# 2_Part_Conveter.net
KiCad netlist of a schematic drawn in Altium Designer
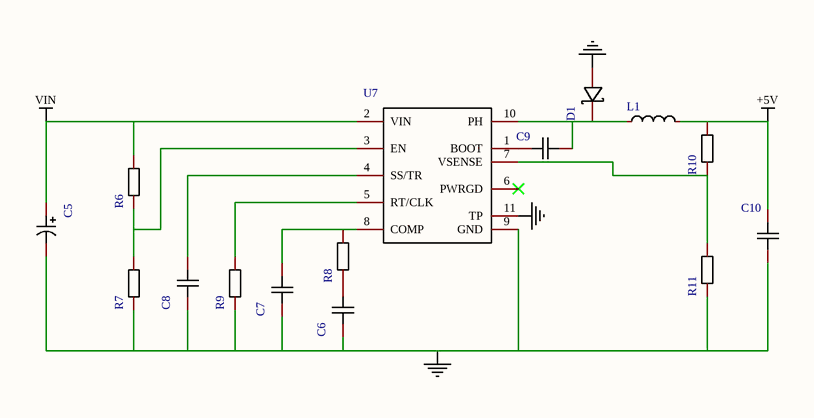
[diagram p0: 2_Part_Conveter.schdoc]

(export (version "E")
  (design (tool "Eeschema 10.0.6"))
  (components
    (comp (ref "C5")
      (value "RVT10UF100V67RV0110_1")
      (description "工作寿命:2000hrs@105℃;")
      (fields
        (field (name "MANUFACTURER") "KNSCHA(科尼盛)")
        (field (name "MANUFACTURER PART") "RVT10UF100V67RV0110")
      )
      (libsource (lib "altium-import") (part "root_3_RVT10UF100V67RV0110_1_"))
    )
    (comp (ref "C6")
      (value "C0603C102K1RAC3083")
      (description "容值:1nF;精度:±10%;额定电压:100V;温度系数:X7R;")
      (fields (field (name "MANUFACTURER") "KEMET(基美)") (field (name "TOLERANCE") "±10%"))
      (libsource (lib "altium-import") (part "root_1_C0603C102K1RAC3083_"))
    )
    (comp (ref "C7")
      (value "C0603C102K1RAC3083")
      (description "容值:1nF;精度:±10%;额定电压:100V;温度系数:X7R;")
      (fields (field (name "MANUFACTURER") "KEMET(基美)") (field (name "TOLERANCE") "±10%"))
      (libsource (lib "altium-import") (part "root_1_C0603C102K1RAC3083_"))
    )
    (comp (ref "C8")
      (value "C0603C102K1RAC3083")
      (description "容值:1nF;精度:±10%;额定电压:100V;温度系数:X7R;")
      (fields (field (name "MANUFACTURER") "KEMET(基美)") (field (name "TOLERANCE") "±10%"))
      (libsource (lib "altium-import") (part "root_1_C0603C102K1RAC3083_"))
    )
    (comp (ref "C9")
      (value "C0603C102K1RAC3083")
      (description "容值:1nF;精度:±10%;额定电压:100V;温度系数:X7R;")
      (fields (field (name "MANUFACTURER") "KEMET(基美)") (field (name "TOLERANCE") "±10%"))
      (libsource (lib "altium-import") (part "root_2_C0603C102K1RAC3083_"))
    )
    (comp (ref "C10")
      (value "GRM32ER60J476ME20L_1")
      (description "容值:47uF;精度:±20%;额定电压:6.3V;温度系数:X5R;")
      (fields
        (field (name "MANUFACTURER") "muRata(村田)")
        (field (name "MANUFACTURER PART") "GRM32ER60J476ME20L")
      )
      (libsource (lib "altium-import") (part "root_0_GRM32ER60J476ME20L_1_"))
    )
    (comp (ref "D1")
      (value "SS24_1")
      (description "直流反向耐压(Vr):40V;平均整流电流(Io):2A;正向压降(Vf):550mV@1A;")
      (fields (field (name "MANUFACTURER") "SINO-IC(光宇睿芯)") (field (name "MANUFACTURER PART") "SS24"))
      (libsource (lib "altium-import") (part "root_1_SS24_1_"))
    )
    (comp (ref "L1")
      (value "CYH74-33UH_1")
      (fields (field (name "MANUFACTURER") "SHOU HAN(首韩)") (field (name "MANUFACTURER PART") "CYH74-33UH"))
      (libsource (lib "altium-import") (part "root_0_CYH74-33UH_1_"))
    )
    (comp (ref "R6")
      (value "CR0603FA5603G_1")
      (description "电阻类型:厚膜电阻;阻值:560kΩ;精度:±1%;功率:1/10W;温度系数:±100ppm/℃;最大工作电压:50V;工作温度范围:-55℃~+125℃;")
      (fields (field (name "MANUFACTURER") "LIZ(丽智电子)") (field (name "MANUFACTURER PART") "CR0603FA5603G"))
      (libsource (lib "altium-import") (part "root_1_CR0603FA5603G_1_"))
    )
    (comp (ref "R7")
      (value "CR0603FA5603G_1")
      (description "电阻类型:厚膜电阻;阻值:560kΩ;精度:±1%;功率:1/10W;温度系数:±100ppm/℃;最大工作电压:50V;工作温度范围:-55℃~+125℃;")
      (fields (field (name "MANUFACTURER") "LIZ(丽智电子)") (field (name "MANUFACTURER PART") "CR0603FA5603G"))
      (libsource (lib "altium-import") (part "root_1_CR0603FA5603G_1_"))
    )
    (comp (ref "R8")
      (value "CR0603FA5603G_1")
      (description "电阻类型:厚膜电阻;阻值:560kΩ;精度:±1%;功率:1/10W;温度系数:±100ppm/℃;最大工作电压:50V;工作温度范围:-55℃~+125℃;")
      (fields (field (name "MANUFACTURER") "LIZ(丽智电子)") (field (name "MANUFACTURER PART") "CR0603FA5603G"))
      (libsource (lib "altium-import") (part "root_1_CR0603FA5603G_1_"))
    )
    (comp (ref "R9")
      (value "CR0603FA5603G_1")
      (description "电阻类型:厚膜电阻;阻值:560kΩ;精度:±1%;功率:1/10W;温度系数:±100ppm/℃;最大工作电压:50V;工作温度范围:-55℃~+125℃;")
      (fields (field (name "MANUFACTURER") "LIZ(丽智电子)") (field (name "MANUFACTURER PART") "CR0603FA5603G"))
      (libsource (lib "altium-import") (part "root_1_CR0603FA5603G_1_"))
    )
    (comp (ref "R10")
      (value "CR0603FA5603G_1")
      (description "电阻类型:厚膜电阻;阻值:560kΩ;精度:±1%;功率:1/10W;温度系数:±100ppm/℃;最大工作电压:50V;工作温度范围:-55℃~+125℃;")
      (fields (field (name "MANUFACTURER") "LIZ(丽智电子)") (field (name "MANUFACTURER PART") "CR0603FA5603G"))
      (libsource (lib "altium-import") (part "root_1_CR0603FA5603G_1_"))
    )
    (comp (ref "R11")
      (value "CR0603FA5603G_1")
      (description "电阻类型:厚膜电阻;阻值:560kΩ;精度:±1%;功率:1/10W;温度系数:±100ppm/℃;最大工作电压:50V;工作温度范围:-55℃~+125℃;")
      (fields (field (name "MANUFACTURER") "LIZ(丽智电子)") (field (name "MANUFACTURER PART") "CR0603FA5603G"))
      (libsource (lib "altium-import") (part "root_1_CR0603FA5603G_1_"))
    )
    (comp (ref "U7")
      (value "TPS54160DGQR_1")
      (description "功能类型:降压型;同步整流:-;输出通道数:-;拓扑结构:-;输入电压:-;输出电流(最大值):-;开关频率:-;")
      (fields (field (name "MANUFACTURER") "TI(德州仪器)") (field (name "MANUFACTURER PART") "TPS54160DGQR"))
      (libsource (lib "altium-import") (part "root_0_TPS54160DGQR_1_"))
    )
  )
  (nets
    (net (code "1") (name "+5V") (class "Default")
      (node (ref "C10") (pin "2") (pinfunction "2_2") (pintype "passive"))
      (node (ref "L1") (pin "2") (pinfunction "2_2") (pintype "passive"))
      (node (ref "R10") (pin "2") (pinfunction "2_2") (pintype "passive"))
    )
    (net (code "2") (name "GND") (class "Default")
      (node (ref "C10") (pin "1") (pinfunction "1_1") (pintype "passive"))
      (node (ref "C5") (pin "2") (pinfunction "2_2") (pintype "passive"))
      (node (ref "C6") (pin "1") (pinfunction "1_1") (pintype "passive"))
      (node (ref "C7") (pin "1") (pinfunction "1_1") (pintype "passive"))
      (node (ref "C8") (pin "1") (pinfunction "1_1") (pintype "passive"))
      (node (ref "D1") (pin "2") (pinfunction "A_2") (pintype "passive"))
      (node (ref "R11") (pin "1") (pinfunction "1_1") (pintype "passive"))
      (node (ref "R7") (pin "1") (pinfunction "1_1") (pintype "passive"))
      (node (ref "R9") (pin "1") (pinfunction "1_1") (pintype "passive"))
      (node (ref "U7") (pin "11") (pinfunction "TP_11") (pintype "passive"))
      (node (ref "U7") (pin "9") (pinfunction "GND_9") (pintype "passive"))
    )
    (net (code "3") (name "Net-(C6-Pad2)") (class "Default")
      (node (ref "C6") (pin "2") (pinfunction "2_2") (pintype "passive"))
      (node (ref "R8") (pin "1") (pinfunction "1_1") (pintype "passive"))
    )
    (net (code "4") (name "Net-(D1-C)") (class "Default")
      (node (ref "C9") (pin "1") (pinfunction "1_1") (pintype "passive"))
      (node (ref "D1") (pin "1") (pinfunction "C_1") (pintype "passive"))
      (node (ref "L1") (pin "1") (pinfunction "1_1") (pintype "passive"))
      (node (ref "U7") (pin "10") (pinfunction "PH_10") (pintype "passive"))
    )
    (net (code "5") (name "Net-(U7-BOOT)") (class "Default")
      (node (ref "C9") (pin "2") (pinfunction "2_2") (pintype "passive"))
      (node (ref "U7") (pin "1") (pinfunction "BOOT_1") (pintype "passive"))
    )
    (net (code "6") (name "Net-(U7-COMP)") (class "Default")
      (node (ref "C7") (pin "2") (pinfunction "2_2") (pintype "passive"))
      (node (ref "R8") (pin "2") (pinfunction "2_2") (pintype "passive"))
      (node (ref "U7") (pin "8") (pinfunction "COMP_8") (pintype "passive"))
    )
    (net (code "7") (name "Net-(U7-EN)") (class "Default")
      (node (ref "R6") (pin "1") (pinfunction "1_1") (pintype "passive"))
      (node (ref "R7") (pin "2") (pinfunction "2_2") (pintype "passive"))
      (node (ref "U7") (pin "3") (pinfunction "EN_3") (pintype "passive"))
    )
    (net (code "8") (name "Net-(U7-RT{slash}CLK)") (class "Default")
      (node (ref "R9") (pin "2") (pinfunction "2_2") (pintype "passive"))
      (node (ref "U7") (pin "5") (pinfunction "RT/CLK_5") (pintype "passive"))
    )
    (net (code "9") (name "Net-(U7-SS{slash}TR)") (class "Default")
      (node (ref "C8") (pin "2") (pinfunction "2_2") (pintype "passive"))
      (node (ref "U7") (pin "4") (pinfunction "SS/TR_4") (pintype "passive"))
    )
    (net (code "10") (name "Net-(U7-VSENSE)") (class "Default")
      (node (ref "R10") (pin "1") (pinfunction "1_1") (pintype "passive"))
      (node (ref "R11") (pin "2") (pinfunction "2_2") (pintype "passive"))
      (node (ref "U7") (pin "7") (pinfunction "VSENSE_7") (pintype "passive"))
    )
    (net (code "11") (name "VIN") (class "Default")
      (node (ref "C5") (pin "1") (pinfunction "1_1") (pintype "passive"))
      (node (ref "R6") (pin "2") (pinfunction "2_2") (pintype "passive"))
      (node (ref "U7") (pin "2") (pinfunction "VIN_2") (pintype "passive"))
    )
    (net (code "12") (name "unconnected-(U7-PWRGD-Pad6)") (class "Default")
      (node (ref "U7") (pin "6") (pinfunction "PWRGD_6") (pintype "passive+no_connect"))
    )
  )
)
